# EEPROM.net
KiCad netlist of a schematic drawn in Altium Designer
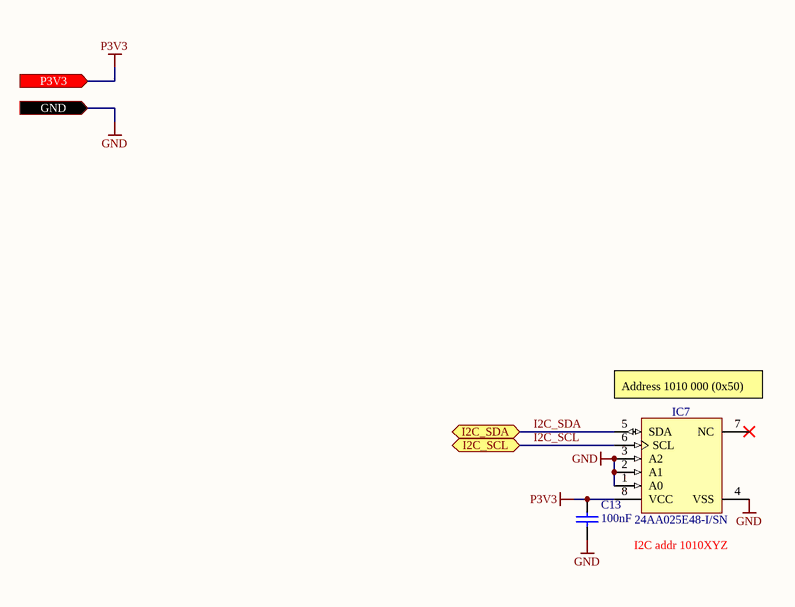
[diagram p0: EEPROM.SchDoc]

(export (version "E")
  (design (tool "Eeschema 10.0.6"))
  (components
    (comp (ref "C13")
      (value "100nF")
      (footprint "CAPC1608X87N")
      (description "Non-polarised capacitor")
      (fields
        (field (name "PART NUMBER") "CC0603_100NF_50V_10%_X5R")
        (field (name "VOLTAGE") "50V")
        (field (name "AUTHOR") "CERN DEM MR")
      )
      (libsource (lib "Capacitors") (part "Capacitor - non polarized"))
    )
    (comp (ref "IC7")
      (value "24AA025E48-I/SN")
      (footprint "SOIC127P600X175-8N")
      (description "1.7V-5.5V, 2K I2C™ Serial EEPROMs with EUI-48™ Node Identity")
      (fields (field (name "MANUFACTURER") "MICROCHIP TECHNOLOGY") (field (name "AUTHOR") "CERN DEM MR"))
      (libsource (lib "ICs And Semiconductors") (part "24AA025E48-I/SN"))
    )
  )
  (nets
    (net (code "1") (name "/I2C_SCL") (class "Default")
      (node (ref "IC7") (pin "6") (pinfunction "SCL_6") (pintype "input"))
    )
    (net (code "2") (name "/I2C_SDA") (class "Default")
      (node (ref "IC7") (pin "5") (pinfunction "SDA_5") (pintype "bidirectional"))
    )
    (net (code "3") (name "GND") (class "Default")
      (node (ref "C13") (pin "2") (pinfunction "2_2") (pintype "passive"))
      (node (ref "IC7") (pin "1") (pinfunction "A0_1") (pintype "input"))
      (node (ref "IC7") (pin "2") (pinfunction "A1_2") (pintype "input"))
      (node (ref "IC7") (pin "3") (pinfunction "A2_3") (pintype "input"))
      (node (ref "IC7") (pin "4") (pinfunction "VSS_4") (pintype "power_in"))
    )
    (net (code "4") (name "P3V3") (class "Default")
      (node (ref "C13") (pin "1") (pinfunction "1_1") (pintype "passive"))
      (node (ref "IC7") (pin "8") (pinfunction "VCC_8") (pintype "power_in"))
    )
    (net (code "5") (name "unconnected-(IC7-NC-Pad7)") (class "Default")
      (node (ref "IC7") (pin "7") (pinfunction "NC_7") (pintype "passive+no_connect"))
    )
  )
)
